# USB_HOST.net
KiCad netlist of a schematic drawn in Altium Designer
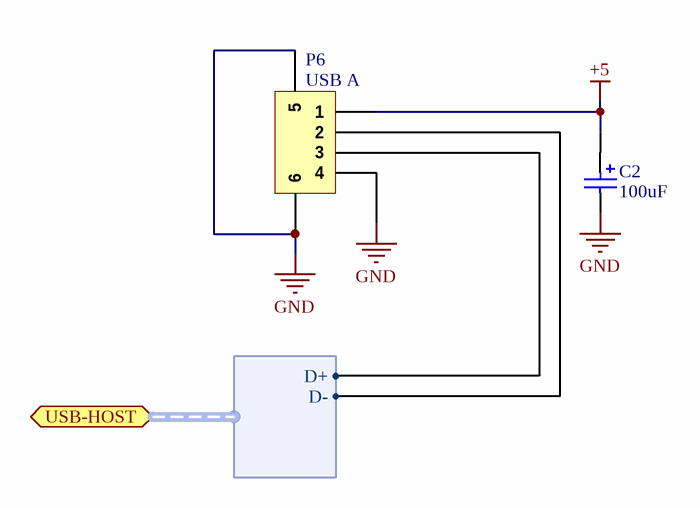
[diagram p0: USB HOST.SchDoc]

(export (version "E")
  (design (tool "Eeschema 10.0.6"))
  (components
    (comp (ref "C2")
      (value "100uF")
      (footprint "Kemet_63")
      (description "Polarized Capacitor")
      (fields
        (field (name "MANUFACTURER") "EPCOS")
        (field (name "MANUFACTURER PART NUMBER") "B41142A4107M")
        (field (name "HAUTEUR") "7.7")
        (field (name "LONGUEUR/HAUTEUR") "7.7")
      )
      (libsource (lib "BRA") (part "Cap Pol 100uF"))
    )
    (comp (ref "P6")
      (value "USB A")
      (footprint "USB  2410 06")
      (description "USB 2.0 Connector A")
      (fields (field (name "MANUFACTURER") "LUMBERG") (field (name "MANUFACTURER PART NUMBER") "2410 06"))
      (libsource (lib "MAIN BOARD CERES") (part "Header 4_1"))
    )
  )
  (nets
    (net (code "2") (name "+5") (class "Default")
      (node (ref "C2") (pin "1") (pinfunction "1_1") (pintype "passive"))
      (node (ref "P6") (pin "1") (pinfunction "1_1") (pintype "passive"))
    )
    (net (code "3") (name "/D+") (class "Default")
      (node (ref "P6") (pin "3") (pinfunction "3_3") (pintype "passive"))
    )
    (net (code "4") (name "/D-") (class "Default")
      (node (ref "P6") (pin "2") (pinfunction "2_2") (pintype "passive"))
    )
    (net (code "6") (name "GND") (class "Default")
      (node (ref "C2") (pin "2") (pinfunction "2_2") (pintype "passive"))
      (node (ref "P6") (pin "4") (pinfunction "4_4") (pintype "passive"))
      (node (ref "P6") (pin "5") (pinfunction "5_5") (pintype "passive"))
      (node (ref "P6") (pin "6") (pinfunction "6_6") (pintype "passive"))
    )
  )
)
